# SCH_Orto-Idroponico_2021-09-27.net
KiCad netlist of a schematic drawn in EasyEDA
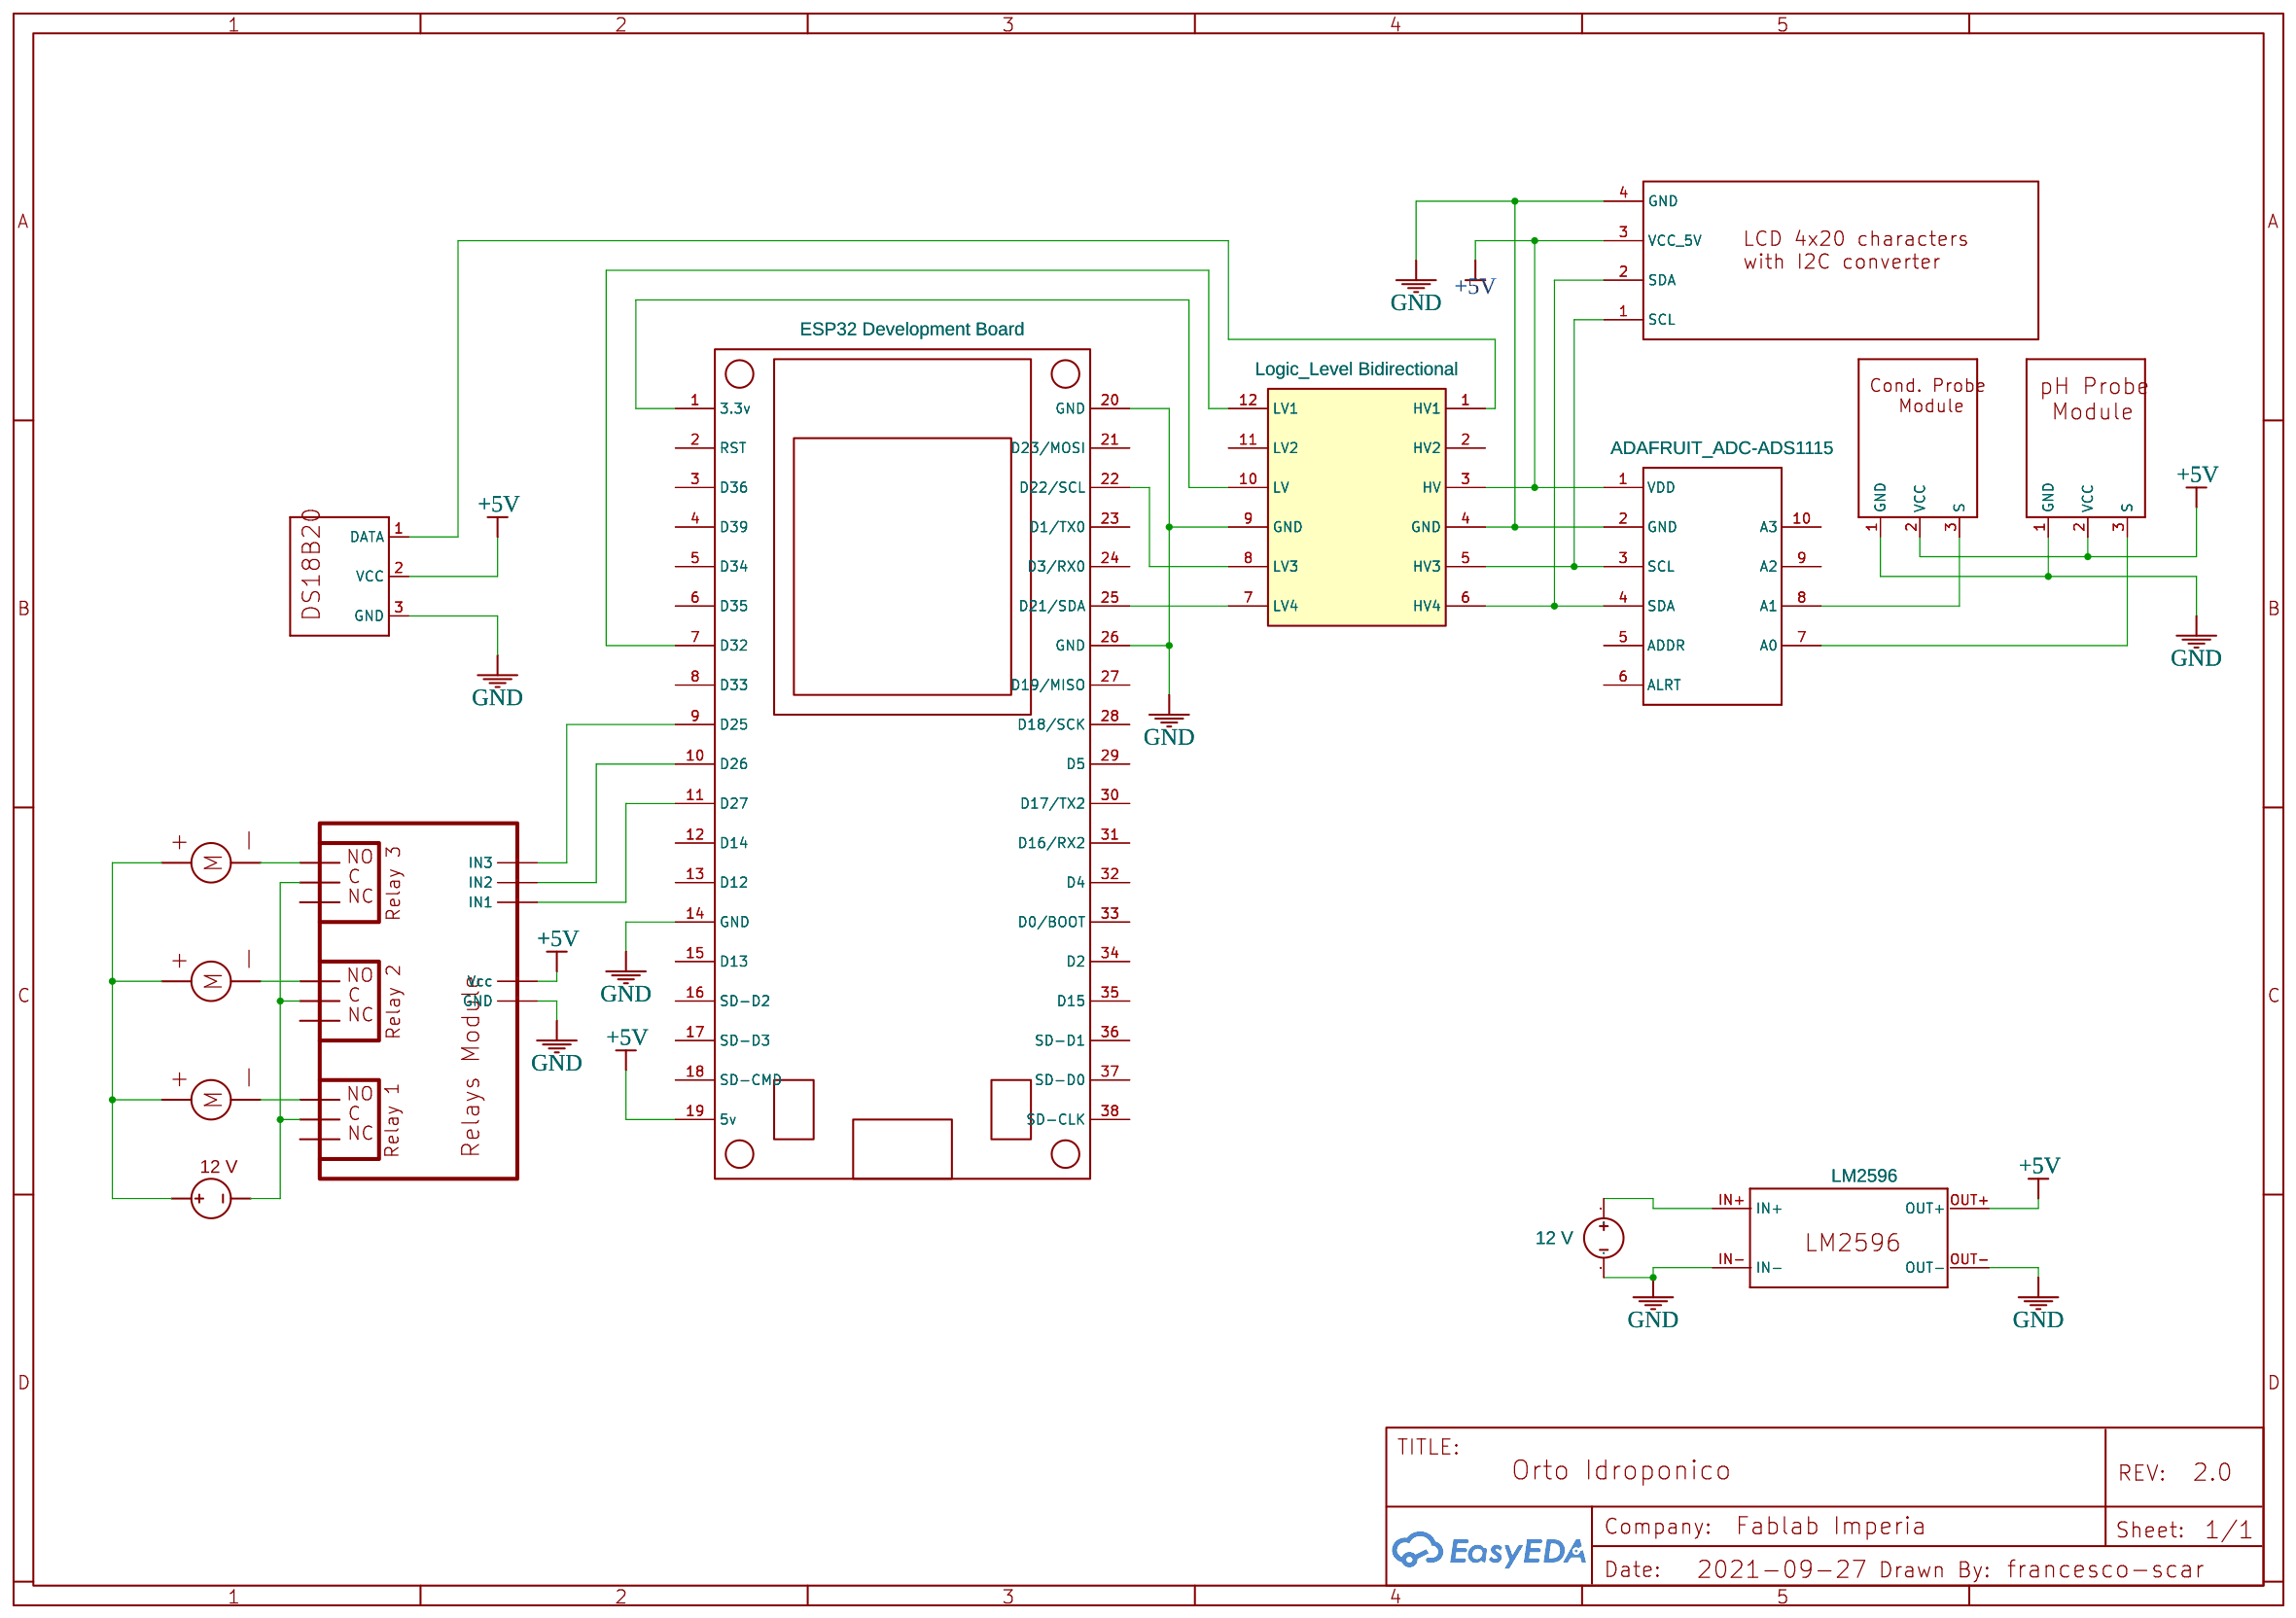
[diagram p0: schematic sheet]

(export (version "E")
  (design (tool "Eeschema 10.0.6"))
  (components
    (comp (ref "2") (value "ADAFRUIT_ADC-ADS1115") (libsource (lib "") (part "ADAFRUIT_ADC-ADS1115")))
    (comp (ref "P2")
      (value "Logic_Level Bidirectional")
      (libsource (lib "") (part "Logic_Level Bidirectional"))
    )
    (comp (ref "REG2") (value "LM2596") (libsource (lib "") (part "LM2596")))
    (comp (ref "T1") (value "DS18B20") (libsource (lib "") (part "DS18B20")))
    (comp (ref "T2") (value "pH probe module") (libsource (lib "") (part "pH probe module")))
    (comp (ref "T3")
      (value "conductivity probe module")
      (libsource (lib "") (part "conductivity probe module"))
    )
    (comp (ref "U1") (value "ESP32 Development Board") (libsource (lib "") (part "ESP32 Development Board")))
    (comp (ref "U2")
      (value "3_RELAYS_MODULE")
      (fields (field (name "BOM_Manufacturer Part") "3 Relays Module"))
      (libsource (lib "") (part "3_RELAYS_MODULE"))
    )
    (comp (ref "U3")
      (value "Nettigo LCD 4x20 I2C")
      (fields (field (name "BOM_Manufacturer Part") "2004A"))
      (libsource (lib "") (part "Nettigo LCD 4x20 I2C"))
    )
    (comp (ref "U4") (value "DC power source no pin") (libsource (lib "") (part "DC power source no pin")))
    (comp (ref "U7") (value "DC Motor no pin") (libsource (lib "") (part "DC Motor no pin")))
    (comp (ref "U8") (value "DC Motor no pin") (libsource (lib "") (part "DC Motor no pin")))
    (comp (ref "U9") (value "DC Motor no pin") (libsource (lib "") (part "DC Motor no pin")))
    (comp (ref "V1") (value "12 V") (libsource (lib "") (part "DC Power Source")))
  )
  (nets
    (net (code "1") (name "+5V") (class "Default")
      (node (ref "2") (pin "1") (pinfunction "VDD_1") (pintype "bidirectional"))
      (node (ref "P2") (pin "3") (pinfunction "HV_3") (pintype "unspecified"))
      (node (ref "REG2") (pin "OUT+") (pinfunction "OUT+_OUT+") (pintype "bidirectional"))
      (node (ref "T1") (pin "2") (pinfunction "VCC_2") (pintype "unspecified"))
      (node (ref "T2") (pin "2") (pinfunction "VCC_2") (pintype "unspecified"))
      (node (ref "T3") (pin "2") (pinfunction "VCC_2") (pintype "unspecified"))
      (node (ref "U1") (pin "19") (pinfunction "5v_19") (pintype "passive"))
      (node (ref "U2") (pin "10") (pinfunction "Vcc_10") (pintype "unspecified"))
      (node (ref "U3") (pin "3") (pinfunction "VCC_5V_3") (pintype "unspecified"))
    )
    (net (code "2") (name "GND") (class "Default")
      (node (ref "2") (pin "2") (pinfunction "GND_2") (pintype "bidirectional"))
      (node (ref "P2") (pin "4") (pinfunction "GND_4") (pintype "unspecified"))
      (node (ref "P2") (pin "9") (pinfunction "GND_9") (pintype "unspecified"))
      (node (ref "REG2") (pin "IN-") (pinfunction "IN-_IN-") (pintype "bidirectional"))
      (node (ref "REG2") (pin "OUT-") (pinfunction "OUT-_OUT-") (pintype "bidirectional"))
      (node (ref "T1") (pin "3") (pinfunction "GND_3") (pintype "passive"))
      (node (ref "T2") (pin "1") (pinfunction "GND_1") (pintype "passive"))
      (node (ref "T3") (pin "1") (pinfunction "GND_1") (pintype "passive"))
      (node (ref "U1") (pin "14") (pinfunction "GND_14") (pintype "passive"))
      (node (ref "U1") (pin "20") (pinfunction "GND_20") (pintype "passive"))
      (node (ref "U1") (pin "26") (pinfunction "GND_26") (pintype "passive"))
      (node (ref "U2") (pin "1") (pinfunction "GND_1") (pintype "unspecified"))
      (node (ref "U3") (pin "4") (pinfunction "GND_4") (pintype "unspecified"))
      (node (ref "V1") (pin "2") (pinfunction "2_2") (pintype "unspecified"))
    )
    (net (code "3") (name "Net-(2-A0)") (class "Default")
      (node (ref "2") (pin "7") (pinfunction "A0_7") (pintype "bidirectional"))
      (node (ref "T2") (pin "3") (pinfunction "S_3") (pintype "passive"))
    )
    (net (code "4") (name "Net-(2-A1)") (class "Default")
      (node (ref "2") (pin "8") (pinfunction "A1_8") (pintype "bidirectional"))
      (node (ref "T3") (pin "3") (pinfunction "S_3") (pintype "passive"))
    )
    (net (code "5") (name "Net-(2-SCL)") (class "Default")
      (node (ref "2") (pin "3") (pinfunction "SCL_3") (pintype "bidirectional"))
      (node (ref "P2") (pin "5") (pinfunction "HV3_5") (pintype "unspecified"))
      (node (ref "U3") (pin "1") (pinfunction "SCL_1") (pintype "unspecified"))
    )
    (net (code "6") (name "Net-(2-SDA)") (class "Default")
      (node (ref "2") (pin "4") (pinfunction "SDA_4") (pintype "bidirectional"))
      (node (ref "P2") (pin "6") (pinfunction "HV4_6") (pintype "unspecified"))
      (node (ref "U3") (pin "2") (pinfunction "SDA_2") (pintype "unspecified"))
    )
    (net (code "7") (name "Net-(P2-HV1)") (class "Default")
      (node (ref "P2") (pin "1") (pinfunction "HV1_1") (pintype "unspecified"))
      (node (ref "T1") (pin "1") (pinfunction "DATA_1") (pintype "passive"))
    )
    (net (code "8") (name "Net-(P2-LV)") (class "Default")
      (node (ref "P2") (pin "10") (pinfunction "LV_10") (pintype "unspecified"))
      (node (ref "U1") (pin "1") (pinfunction "3.3v_1") (pintype "passive"))
    )
    (net (code "9") (name "Net-(P2-LV1)") (class "Default")
      (node (ref "P2") (pin "12") (pinfunction "LV1_12") (pintype "unspecified"))
      (node (ref "U1") (pin "7") (pinfunction "D32_7") (pintype "bidirectional"))
    )
    (net (code "10") (name "Net-(P2-LV3)") (class "Default")
      (node (ref "P2") (pin "8") (pinfunction "LV3_8") (pintype "unspecified"))
      (node (ref "U1") (pin "22") (pinfunction "D22/SCL_22") (pintype "bidirectional"))
    )
    (net (code "11") (name "Net-(P2-LV4)") (class "Default")
      (node (ref "P2") (pin "7") (pinfunction "LV4_7") (pintype "unspecified"))
      (node (ref "U1") (pin "25") (pinfunction "D21/SDA_25") (pintype "bidirectional"))
    )
    (net (code "12") (name "Net-(REG2-PadIN+)") (class "Default")
      (node (ref "REG2") (pin "IN+") (pinfunction "IN+_IN+") (pintype "bidirectional"))
      (node (ref "V1") (pin "1") (pinfunction "1_1") (pintype "unspecified"))
    )
    (net (code "13") (name "Net-(U1-D25)") (class "Default")
      (node (ref "U1") (pin "9") (pinfunction "D25_9") (pintype "bidirectional"))
      (node (ref "U2") (pin "4") (pinfunction "IN3_4") (pintype "unspecified"))
    )
    (net (code "14") (name "Net-(U1-D26)") (class "Default")
      (node (ref "U1") (pin "10") (pinfunction "D26_10") (pintype "bidirectional"))
      (node (ref "U2") (pin "3") (pinfunction "IN2_3") (pintype "unspecified"))
    )
    (net (code "15") (name "Net-(U1-D27)") (class "Default")
      (node (ref "U1") (pin "11") (pinfunction "D27_11") (pintype "bidirectional"))
      (node (ref "U2") (pin "2") (pinfunction "IN1_2") (pintype "unspecified"))
    )
    (net (code "16") (name "unconnected-(2-A2-Pad9)") (class "Default")
      (node (ref "2") (pin "9") (pinfunction "A2_9") (pintype "bidirectional"))
    )
    (net (code "17") (name "unconnected-(2-A3-Pad10)") (class "Default")
      (node (ref "2") (pin "10") (pinfunction "A3_10") (pintype "bidirectional"))
    )
    (net (code "18") (name "unconnected-(2-ADDR-Pad5)") (class "Default")
      (node (ref "2") (pin "5") (pinfunction "ADDR_5") (pintype "bidirectional"))
    )
    (net (code "19") (name "unconnected-(2-ALRT-Pad6)") (class "Default")
      (node (ref "2") (pin "6") (pinfunction "ALRT_6") (pintype "bidirectional"))
    )
    (net (code "20") (name "unconnected-(P2-HV2-Pad2)") (class "Default")
      (node (ref "P2") (pin "2") (pinfunction "HV2_2") (pintype "unspecified"))
    )
    (net (code "21") (name "unconnected-(P2-LV2-Pad11)") (class "Default")
      (node (ref "P2") (pin "11") (pinfunction "LV2_11") (pintype "unspecified"))
    )
    (net (code "22") (name "unconnected-(U1-D0{slash}BOOT-Pad33)") (class "Default")
      (node (ref "U1") (pin "33") (pinfunction "D0/BOOT_33") (pintype "bidirectional"))
    )
    (net (code "23") (name "unconnected-(U1-D1{slash}TX0-Pad23)") (class "Default")
      (node (ref "U1") (pin "23") (pinfunction "D1/TX0_23") (pintype "bidirectional"))
    )
    (net (code "24") (name "unconnected-(U1-D2-Pad34)") (class "Default")
      (node (ref "U1") (pin "34") (pinfunction "D2_34") (pintype "bidirectional"))
    )
    (net (code "25") (name "unconnected-(U1-D3{slash}RX0-Pad24)") (class "Default")
      (node (ref "U1") (pin "24") (pinfunction "D3/RX0_24") (pintype "bidirectional"))
    )
    (net (code "26") (name "unconnected-(U1-D4-Pad32)") (class "Default")
      (node (ref "U1") (pin "32") (pinfunction "D4_32") (pintype "bidirectional"))
    )
    (net (code "27") (name "unconnected-(U1-D5-Pad29)") (class "Default")
      (node (ref "U1") (pin "29") (pinfunction "D5_29") (pintype "bidirectional"))
    )
    (net (code "28") (name "unconnected-(U1-D12-Pad13)") (class "Default")
      (node (ref "U1") (pin "13") (pinfunction "D12_13") (pintype "bidirectional"))
    )
    (net (code "29") (name "unconnected-(U1-D13-Pad15)") (class "Default")
      (node (ref "U1") (pin "15") (pinfunction "D13_15") (pintype "bidirectional"))
    )
    (net (code "30") (name "unconnected-(U1-D14-Pad12)") (class "Default")
      (node (ref "U1") (pin "12") (pinfunction "D14_12") (pintype "bidirectional"))
    )
    (net (code "31") (name "unconnected-(U1-D15-Pad35)") (class "Default")
      (node (ref "U1") (pin "35") (pinfunction "D15_35") (pintype "bidirectional"))
    )
    (net (code "32") (name "unconnected-(U1-D16{slash}RX2-Pad31)") (class "Default")
      (node (ref "U1") (pin "31") (pinfunction "D16/RX2_31") (pintype "bidirectional"))
    )
    (net (code "33") (name "unconnected-(U1-D17{slash}TX2-Pad30)") (class "Default")
      (node (ref "U1") (pin "30") (pinfunction "D17/TX2_30") (pintype "bidirectional"))
    )
    (net (code "34") (name "unconnected-(U1-D18{slash}SCK-Pad28)") (class "Default")
      (node (ref "U1") (pin "28") (pinfunction "D18/SCK_28") (pintype "bidirectional"))
    )
    (net (code "35") (name "unconnected-(U1-D19{slash}MISO-Pad27)") (class "Default")
      (node (ref "U1") (pin "27") (pinfunction "D19/MISO_27") (pintype "bidirectional"))
    )
    (net (code "36") (name "unconnected-(U1-D23{slash}MOSI-Pad21)") (class "Default")
      (node (ref "U1") (pin "21") (pinfunction "D23/MOSI_21") (pintype "bidirectional"))
    )
    (net (code "37") (name "unconnected-(U1-D33-Pad8)") (class "Default")
      (node (ref "U1") (pin "8") (pinfunction "D33_8") (pintype "bidirectional"))
    )
    (net (code "38") (name "unconnected-(U1-D34-Pad5)") (class "Default")
      (node (ref "U1") (pin "5") (pinfunction "D34_5") (pintype "bidirectional"))
    )
    (net (code "39") (name "unconnected-(U1-D35-Pad6)") (class "Default")
      (node (ref "U1") (pin "6") (pinfunction "D35_6") (pintype "bidirectional"))
    )
    (net (code "40") (name "unconnected-(U1-D36-Pad3)") (class "Default")
      (node (ref "U1") (pin "3") (pinfunction "D36_3") (pintype "bidirectional"))
    )
    (net (code "41") (name "unconnected-(U1-D39-Pad4)") (class "Default")
      (node (ref "U1") (pin "4") (pinfunction "D39_4") (pintype "bidirectional"))
    )
    (net (code "42") (name "unconnected-(U1-RST-Pad2)") (class "Default")
      (node (ref "U1") (pin "2") (pinfunction "RST_2") (pintype "bidirectional"))
    )
    (net (code "43") (name "unconnected-(U1-SD-CLK-Pad38)") (class "Default")
      (node (ref "U1") (pin "38") (pinfunction "SD-CLK_38") (pintype "bidirectional"))
    )
    (net (code "44") (name "unconnected-(U1-SD-CMD-Pad18)") (class "Default")
      (node (ref "U1") (pin "18") (pinfunction "SD-CMD_18") (pintype "bidirectional"))
    )
    (net (code "45") (name "unconnected-(U1-SD-D0-Pad37)") (class "Default")
      (node (ref "U1") (pin "37") (pinfunction "SD-D0_37") (pintype "bidirectional"))
    )
    (net (code "46") (name "unconnected-(U1-SD-D1-Pad36)") (class "Default")
      (node (ref "U1") (pin "36") (pinfunction "SD-D1_36") (pintype "bidirectional"))
    )
    (net (code "47") (name "unconnected-(U1-SD-D2-Pad16)") (class "Default")
      (node (ref "U1") (pin "16") (pinfunction "SD-D2_16") (pintype "bidirectional"))
    )
    (net (code "48") (name "unconnected-(U1-SD-D3-Pad17)") (class "Default")
      (node (ref "U1") (pin "17") (pinfunction "SD-D3_17") (pintype "bidirectional"))
    )
  )
)
